# OperantFEDv4.net
KiCad netlist of a schematic drawn in EAGLE
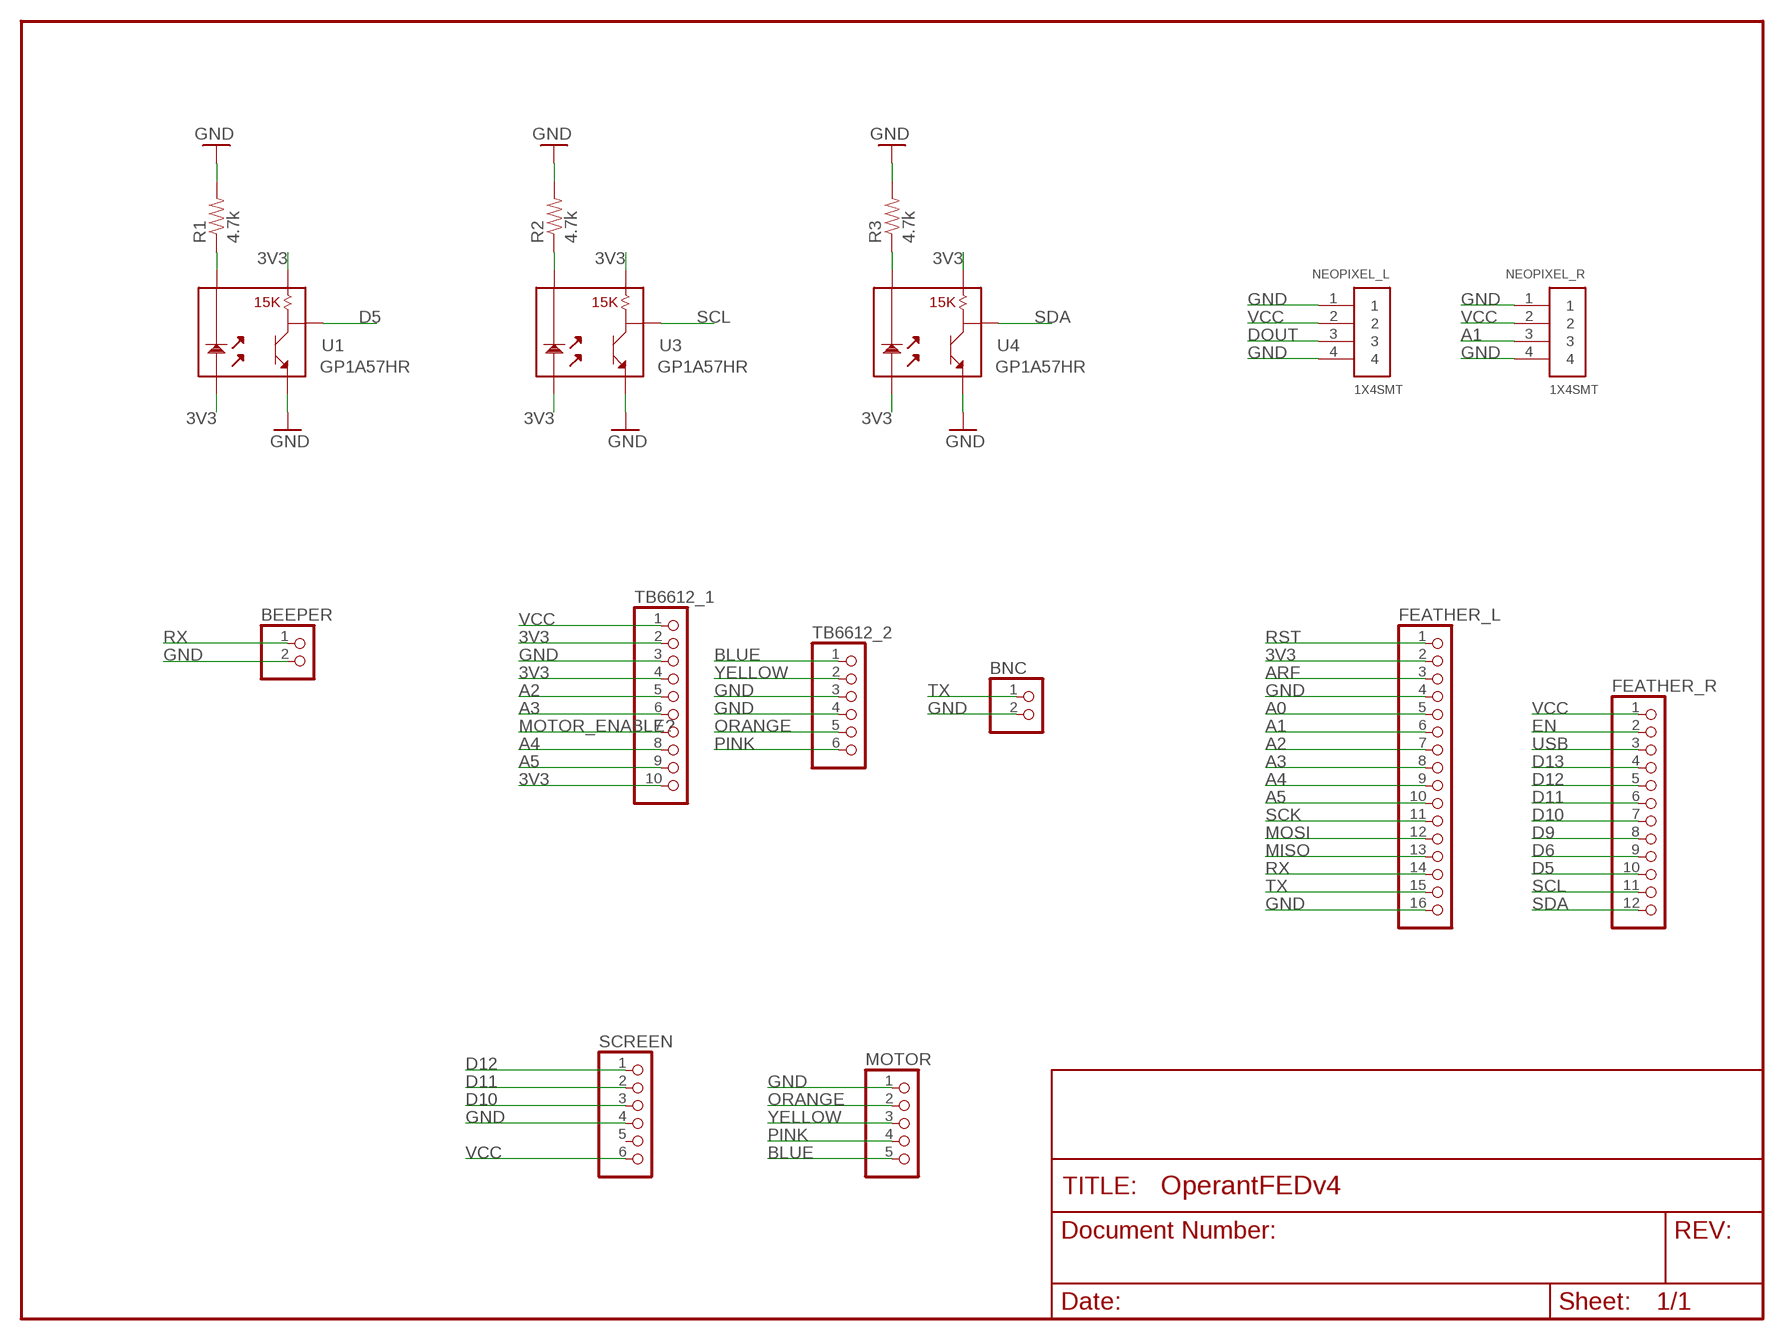
[diagram p0: schematic, sheet 1]

(export (version "E")
  (design (tool "Eeschema 10.0.6"))
  (components
    (comp (ref "BEEPER")
      (value "PINHD-1X2")
      (footprint "eagle-import:1X02")
      (libsource (lib "eagle-import") (part "PINHD-1X2"))
    )
    (comp (ref "BNC")
      (value "PINHD-1X2")
      (footprint "eagle-import:1X02")
      (libsource (lib "eagle-import") (part "PINHD-1X2"))
    )
    (comp (ref "FEATHER_L")
      (value "PINHD-1X16")
      (footprint "eagle-import:1X16")
      (libsource (lib "eagle-import") (part "PINHD-1X16"))
    )
    (comp (ref "FEATHER_R")
      (value "PINHD-1X12")
      (footprint "eagle-import:1X12")
      (libsource (lib "eagle-import") (part "PINHD-1X12"))
    )
    (comp (ref "MOTOR")
      (value "PINHD-1X5")
      (footprint "eagle-import:1X05")
      (libsource (lib "eagle-import") (part "PINHD-1X5"))
    )
    (comp (ref "NEOPIXEL_L")
      (value "1X4SMT")
      (footprint "eagle-import:1X4-SMT")
      (libsource (lib "eagle-import") (part "1X4SMT"))
    )
    (comp (ref "NEOPIXEL_R")
      (value "1X4SMT")
      (footprint "eagle-import:1X4-SMT")
      (libsource (lib "eagle-import") (part "1X4SMT"))
    )
    (comp (ref "R1")
      (value "4.7k")
      (footprint "eagle-import:AXIAL-0.3")
      (libsource (lib "eagle-import") (part "RESISTORPTH1"))
    )
    (comp (ref "R2")
      (value "4.7k")
      (footprint "eagle-import:AXIAL-0.3")
      (libsource (lib "eagle-import") (part "RESISTORPTH1"))
    )
    (comp (ref "R3")
      (value "4.7k")
      (footprint "eagle-import:AXIAL-0.3")
      (libsource (lib "eagle-import") (part "RESISTORPTH1"))
    )
    (comp (ref "SCREEN")
      (value "PINHD-1X6")
      (footprint "eagle-import:1X06")
      (libsource (lib "eagle-import") (part "PINHD-1X6"))
    )
    (comp (ref "TB6612_1")
      (value "PINHD-1X10")
      (footprint "eagle-import:1X10")
      (libsource (lib "eagle-import") (part "PINHD-1X10"))
    )
    (comp (ref "TB6612_2")
      (value "PINHD-1X6")
      (footprint "eagle-import:1X06")
      (libsource (lib "eagle-import") (part "PINHD-1X6"))
    )
    (comp (ref "U1")
      (value "GP1A57HR")
      (footprint "eagle-import:GP1A57HR")
      (libsource (lib "eagle-import") (part "GP1A57HR"))
    )
    (comp (ref "U3")
      (value "GP1A57HR")
      (footprint "eagle-import:GP1A57HR")
      (libsource (lib "eagle-import") (part "GP1A57HR"))
    )
    (comp (ref "U4")
      (value "GP1A57HR")
      (footprint "eagle-import:GP1A57HR")
      (libsource (lib "eagle-import") (part "GP1A57HR"))
    )
  )
  (nets
    (net (code "1") (name "/3V3") (class "Default")
      (node (ref "FEATHER_L") (pin "2") (pinfunction "2_2") (pintype "passive"))
      (node (ref "TB6612_1") (pin "10") (pinfunction "10_10") (pintype "passive"))
      (node (ref "TB6612_1") (pin "2") (pinfunction "2_2") (pintype "passive"))
      (node (ref "TB6612_1") (pin "4") (pinfunction "4_4") (pintype "passive"))
      (node (ref "U1") (pin "1") (pinfunction "1_1") (pintype "bidirectional"))
      (node (ref "U1") (pin "3") (pinfunction "3_3") (pintype "bidirectional"))
      (node (ref "U3") (pin "1") (pinfunction "1_1") (pintype "bidirectional"))
      (node (ref "U3") (pin "3") (pinfunction "3_3") (pintype "bidirectional"))
      (node (ref "U4") (pin "1") (pinfunction "1_1") (pintype "bidirectional"))
      (node (ref "U4") (pin "3") (pinfunction "3_3") (pintype "bidirectional"))
    )
    (net (code "2") (name "/A0") (class "Default")
      (node (ref "FEATHER_L") (pin "5") (pinfunction "5_5") (pintype "passive"))
    )
    (net (code "3") (name "/A1") (class "Default")
      (node (ref "FEATHER_L") (pin "6") (pinfunction "6_6") (pintype "passive"))
      (node (ref "NEOPIXEL_R") (pin "3") (pinfunction "3_3") (pintype "bidirectional"))
    )
    (net (code "4") (name "/A2") (class "Default")
      (node (ref "FEATHER_L") (pin "7") (pinfunction "7_7") (pintype "passive"))
      (node (ref "TB6612_1") (pin "5") (pinfunction "5_5") (pintype "passive"))
    )
    (net (code "5") (name "/A3") (class "Default")
      (node (ref "FEATHER_L") (pin "8") (pinfunction "8_8") (pintype "passive"))
      (node (ref "TB6612_1") (pin "6") (pinfunction "6_6") (pintype "passive"))
    )
    (net (code "6") (name "/A4") (class "Default")
      (node (ref "FEATHER_L") (pin "9") (pinfunction "9_9") (pintype "passive"))
      (node (ref "TB6612_1") (pin "8") (pinfunction "8_8") (pintype "passive"))
    )
    (net (code "7") (name "/A5") (class "Default")
      (node (ref "FEATHER_L") (pin "10") (pinfunction "10_10") (pintype "passive"))
      (node (ref "TB6612_1") (pin "9") (pinfunction "9_9") (pintype "passive"))
    )
    (net (code "8") (name "/ARF") (class "Default")
      (node (ref "FEATHER_L") (pin "3") (pinfunction "3_3") (pintype "passive"))
    )
    (net (code "9") (name "/BLUE") (class "Default")
      (node (ref "MOTOR") (pin "5") (pinfunction "5_5") (pintype "passive"))
      (node (ref "TB6612_2") (pin "1") (pinfunction "1_1") (pintype "passive"))
    )
    (net (code "10") (name "/D5") (class "Default")
      (node (ref "FEATHER_R") (pin "10") (pinfunction "10_10") (pintype "passive"))
      (node (ref "U1") (pin "4") (pinfunction "4_4") (pintype "bidirectional"))
    )
    (net (code "11") (name "/D6") (class "Default")
      (node (ref "FEATHER_R") (pin "9") (pinfunction "9_9") (pintype "passive"))
    )
    (net (code "12") (name "/D9") (class "Default")
      (node (ref "FEATHER_R") (pin "8") (pinfunction "8_8") (pintype "passive"))
    )
    (net (code "13") (name "/D10") (class "Default")
      (node (ref "FEATHER_R") (pin "7") (pinfunction "7_7") (pintype "passive"))
      (node (ref "SCREEN") (pin "3") (pinfunction "3_3") (pintype "passive"))
    )
    (net (code "14") (name "/D11") (class "Default")
      (node (ref "FEATHER_R") (pin "6") (pinfunction "6_6") (pintype "passive"))
      (node (ref "SCREEN") (pin "2") (pinfunction "2_2") (pintype "passive"))
    )
    (net (code "15") (name "/D12") (class "Default")
      (node (ref "FEATHER_R") (pin "5") (pinfunction "5_5") (pintype "passive"))
      (node (ref "SCREEN") (pin "1") (pinfunction "1_1") (pintype "passive"))
    )
    (net (code "16") (name "/D13") (class "Default")
      (node (ref "FEATHER_R") (pin "4") (pinfunction "4_4") (pintype "passive"))
    )
    (net (code "17") (name "/DOUT") (class "Default")
      (node (ref "NEOPIXEL_L") (pin "3") (pinfunction "3_3") (pintype "bidirectional"))
    )
    (net (code "18") (name "/EN") (class "Default")
      (node (ref "FEATHER_R") (pin "2") (pinfunction "2_2") (pintype "passive"))
    )
    (net (code "19") (name "/MISO") (class "Default")
      (node (ref "FEATHER_L") (pin "13") (pinfunction "13_13") (pintype "passive"))
    )
    (net (code "20") (name "/MOSI") (class "Default")
      (node (ref "FEATHER_L") (pin "12") (pinfunction "12_12") (pintype "passive"))
    )
    (net (code "21") (name "/MOTOR_ENABLE?") (class "Default")
      (node (ref "TB6612_1") (pin "7") (pinfunction "7_7") (pintype "passive"))
    )
    (net (code "22") (name "/ORANGE") (class "Default")
      (node (ref "MOTOR") (pin "2") (pinfunction "2_2") (pintype "passive"))
      (node (ref "TB6612_2") (pin "5") (pinfunction "5_5") (pintype "passive"))
    )
    (net (code "23") (name "/PINK") (class "Default")
      (node (ref "MOTOR") (pin "4") (pinfunction "4_4") (pintype "passive"))
      (node (ref "TB6612_2") (pin "6") (pinfunction "6_6") (pintype "passive"))
    )
    (net (code "24") (name "/RST") (class "Default")
      (node (ref "FEATHER_L") (pin "1") (pinfunction "1_1") (pintype "passive"))
    )
    (net (code "25") (name "/RX") (class "Default")
      (node (ref "BEEPER") (pin "1") (pinfunction "1_1") (pintype "passive"))
      (node (ref "FEATHER_L") (pin "14") (pinfunction "14_14") (pintype "passive"))
    )
    (net (code "26") (name "/SCK") (class "Default")
      (node (ref "FEATHER_L") (pin "11") (pinfunction "11_11") (pintype "passive"))
    )
    (net (code "27") (name "/SCL") (class "Default")
      (node (ref "FEATHER_R") (pin "11") (pinfunction "11_11") (pintype "passive"))
      (node (ref "U3") (pin "4") (pinfunction "4_4") (pintype "bidirectional"))
    )
    (net (code "28") (name "/SDA") (class "Default")
      (node (ref "FEATHER_R") (pin "12") (pinfunction "12_12") (pintype "passive"))
      (node (ref "U4") (pin "4") (pinfunction "4_4") (pintype "bidirectional"))
    )
    (net (code "29") (name "/TX") (class "Default")
      (node (ref "BNC") (pin "1") (pinfunction "1_1") (pintype "passive"))
      (node (ref "FEATHER_L") (pin "15") (pinfunction "15_15") (pintype "passive"))
    )
    (net (code "30") (name "/USB") (class "Default")
      (node (ref "FEATHER_R") (pin "3") (pinfunction "3_3") (pintype "passive"))
    )
    (net (code "31") (name "/VCC") (class "Default")
      (node (ref "FEATHER_R") (pin "1") (pinfunction "1_1") (pintype "passive"))
      (node (ref "NEOPIXEL_L") (pin "2") (pinfunction "2_2") (pintype "bidirectional"))
      (node (ref "NEOPIXEL_R") (pin "2") (pinfunction "2_2") (pintype "bidirectional"))
      (node (ref "SCREEN") (pin "6") (pinfunction "6_6") (pintype "passive"))
      (node (ref "TB6612_1") (pin "1") (pinfunction "1_1") (pintype "passive"))
    )
    (net (code "32") (name "/YELLOW") (class "Default")
      (node (ref "MOTOR") (pin "3") (pinfunction "3_3") (pintype "passive"))
      (node (ref "TB6612_2") (pin "2") (pinfunction "2_2") (pintype "passive"))
    )
    (net (code "33") (name "GND") (class "Default")
      (node (ref "BEEPER") (pin "2") (pinfunction "2_2") (pintype "passive"))
      (node (ref "BNC") (pin "2") (pinfunction "2_2") (pintype "passive"))
      (node (ref "FEATHER_L") (pin "16") (pinfunction "16_16") (pintype "passive"))
      (node (ref "FEATHER_L") (pin "4") (pinfunction "4_4") (pintype "passive"))
      (node (ref "MOTOR") (pin "1") (pinfunction "1_1") (pintype "passive"))
      (node (ref "NEOPIXEL_L") (pin "1") (pinfunction "1_1") (pintype "bidirectional"))
      (node (ref "NEOPIXEL_L") (pin "4") (pinfunction "4_4") (pintype "bidirectional"))
      (node (ref "NEOPIXEL_R") (pin "1") (pinfunction "1_1") (pintype "bidirectional"))
      (node (ref "NEOPIXEL_R") (pin "4") (pinfunction "4_4") (pintype "bidirectional"))
      (node (ref "R1") (pin "P$2") (pinfunction "2_P$2") (pintype "passive"))
      (node (ref "R2") (pin "P$2") (pinfunction "2_P$2") (pintype "passive"))
      (node (ref "R3") (pin "P$2") (pinfunction "2_P$2") (pintype "passive"))
      (node (ref "SCREEN") (pin "4") (pinfunction "4_4") (pintype "passive"))
      (node (ref "TB6612_1") (pin "3") (pinfunction "3_3") (pintype "passive"))
      (node (ref "TB6612_2") (pin "3") (pinfunction "3_3") (pintype "passive"))
      (node (ref "TB6612_2") (pin "4") (pinfunction "4_4") (pintype "passive"))
      (node (ref "U1") (pin "5") (pinfunction "5_5") (pintype "bidirectional"))
      (node (ref "U3") (pin "5") (pinfunction "5_5") (pintype "bidirectional"))
      (node (ref "U4") (pin "5") (pinfunction "5_5") (pintype "bidirectional"))
    )
    (net (code "34") (name "Net-(R1-1)") (class "Default")
      (node (ref "R1") (pin "P$1") (pinfunction "1_P$1") (pintype "passive"))
      (node (ref "U1") (pin "2") (pinfunction "2_2") (pintype "bidirectional"))
    )
    (net (code "35") (name "Net-(R2-1)") (class "Default")
      (node (ref "R2") (pin "P$1") (pinfunction "1_P$1") (pintype "passive"))
      (node (ref "U3") (pin "2") (pinfunction "2_2") (pintype "bidirectional"))
    )
    (net (code "36") (name "Net-(R3-1)") (class "Default")
      (node (ref "R3") (pin "P$1") (pinfunction "1_P$1") (pintype "passive"))
      (node (ref "U4") (pin "2") (pinfunction "2_2") (pintype "bidirectional"))
    )
    (net (code "37") (name "unconnected-(SCREEN-Pad5)") (class "Default")
      (node (ref "SCREEN") (pin "5") (pinfunction "5_5") (pintype "passive"))
    )
  )
)
